# Sheet1.net
KiCad netlist of a schematic drawn in Altium Designer
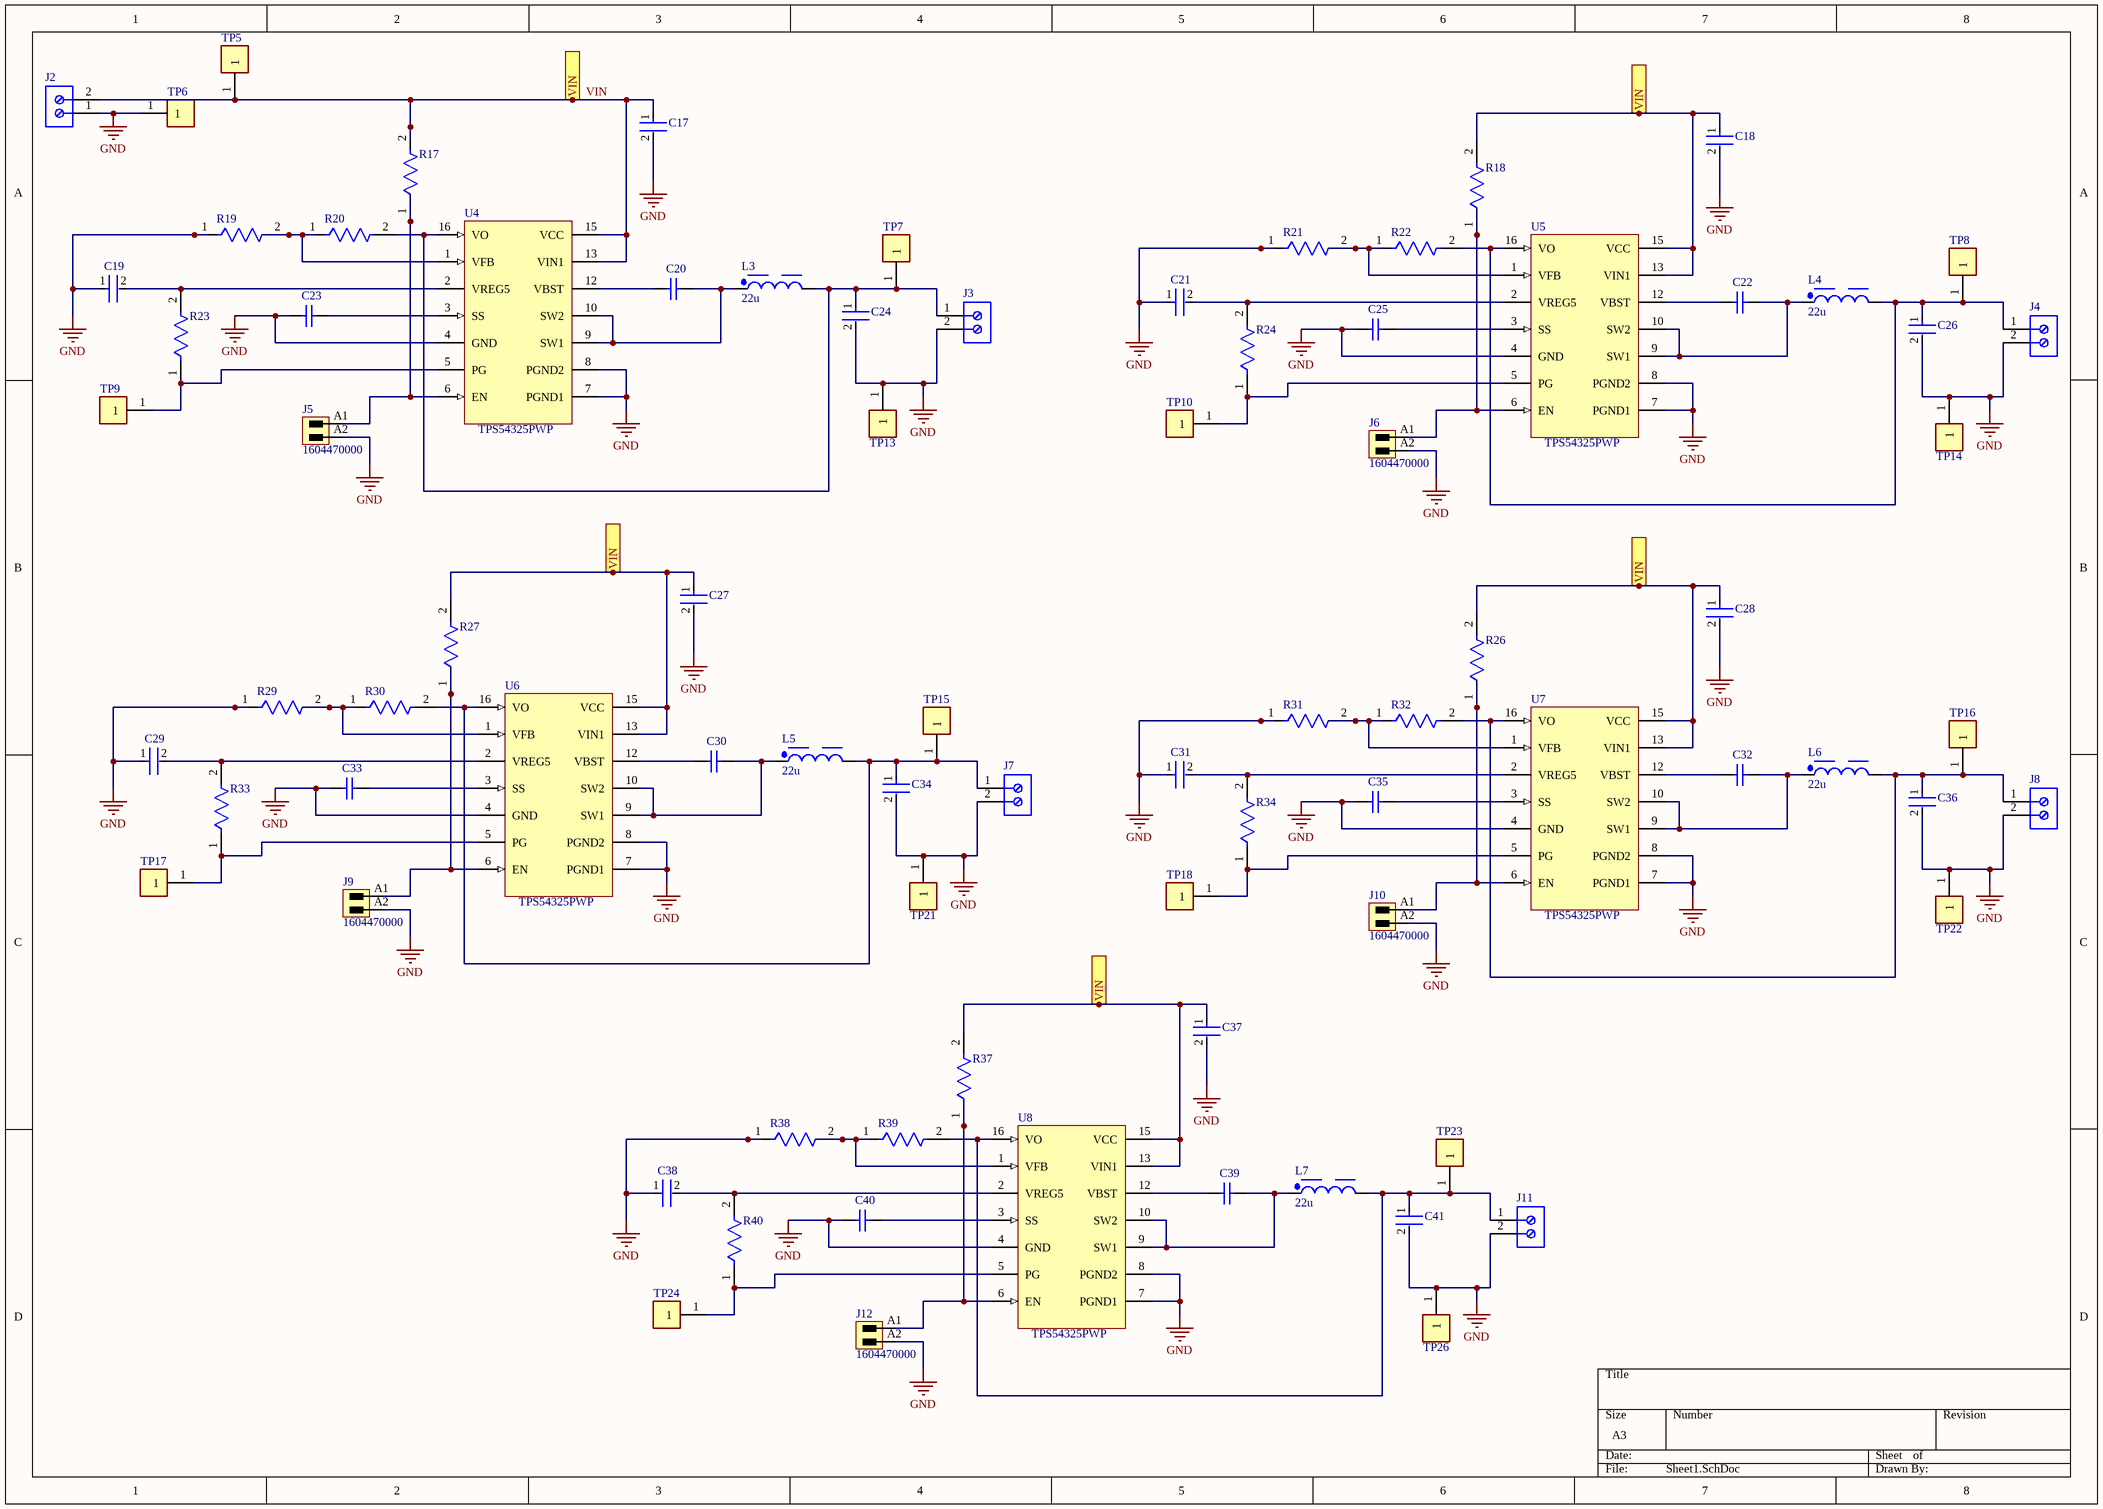
[diagram p0: Sheet1.SchDoc]

(export (version "E")
  (design (tool "Eeschema 10.0.6"))
  (components
    (comp (ref "C17")
      (value "C3216X5R1C106K160AA")
      (footprint "FP-C3216-160-0_2-IPC_C")
      (description "Multilayer Ceramic Capacitors 10uF ±10% 16V X5R SMD 1206")
      (fields (field (name "VOLTAGE") "16V") (field (name "TOLERANCE") "10%"))
      (libsource (lib "Altium Content Vault") (part "11868f565c42a9108669ba33697ecf6"))
    )
    (comp (ref "C18")
      (value "C3216X5R1C106K160AA")
      (footprint "FP-C3216-160-0_2-IPC_C")
      (description "Multilayer Ceramic Capacitors 10uF ±10% 16V X5R SMD 1206")
      (fields (field (name "VOLTAGE") "16V") (field (name "TOLERANCE") "10%"))
      (libsource (lib "Altium Content Vault") (part "11868f565c42a9108669ba33697ecf6"))
    )
    (comp (ref "C19")
      (value "0603YC105KAT2A")
      (footprint "FP-0603-L_1_6_0_15-W_0_81-IPC_C")
      (description "General Purpose Ceramic Capacitor, 0603, 1uF, 10%, X7R, 15%, 16V")
      (fields (field (name "TOLERANCE") "10%") (field (name "VOLTAGE") "16V"))
      (libsource (lib "Altium Content Vault") (part "02cd4be3c70576c341d710602a673aa"))
    )
    (comp (ref "C20")
      (value "GRM188R71H104KA93D")
      (footprint "CAPC1608X90X35ML10T15")
      (description "Chip Capacitor, 0.1 uF, +/- 10%, 50 V, -55 to 125 degC, 0603 (1608 Metric), RoHS, Tape and Reel")
      (fields (field (name "TOLERANCE") "10%") (field (name "VOLTAGE") "50V"))
      (libsource (lib "Altium Content Vault") (part "CAP-NP-2"))
    )
    (comp (ref "C21")
      (value "0603YC105KAT2A")
      (footprint "FP-0603-L_1_6_0_15-W_0_81-IPC_C")
      (description "General Purpose Ceramic Capacitor, 0603, 1uF, 10%, X7R, 15%, 16V")
      (fields (field (name "TOLERANCE") "10%") (field (name "VOLTAGE") "16V"))
      (libsource (lib "Altium Content Vault") (part "02cd4be3c70576c341d710602a673aa"))
    )
    (comp (ref "C22")
      (value "GRM188R71H104KA93D")
      (footprint "CAPC1608X90X35ML10T15")
      (description "Chip Capacitor, 0.1 uF, +/- 10%, 50 V, -55 to 125 degC, 0603 (1608 Metric), RoHS, Tape and Reel")
      (fields (field (name "TOLERANCE") "10%") (field (name "VOLTAGE") "50V"))
      (libsource (lib "Altium Content Vault") (part "CAP-NP-2"))
    )
    (comp (ref "C23")
      (value "GRM188R71H104KA93D")
      (footprint "CAPC1608X90X35ML10T15")
      (description "Chip Capacitor, 0.1 uF, +/- 10%, 50 V, -55 to 125 degC, 0603 (1608 Metric), RoHS, Tape and Reel")
      (fields (field (name "TOLERANCE") "10%") (field (name "VOLTAGE") "50V"))
      (libsource (lib "Altium Content Vault") (part "CAP-NP-2"))
    )
    (comp (ref "C24")
      (value "GRM21BR60J226ME39L")
      (footprint "FP-GRM21B-0_15-MFG")
      (description "Chip Multilayer Ceramic Capacitors for General Purpose, 0805, 22uF, X5R, 15%, 20%, 6.3V")
      (fields (field (name "VOLTAGE") "6.3V") (field (name "TOLERANCE") "20%"))
      (libsource (lib "Altium Content Vault") (part "b4654b650e69147ec39a6b967a45e02"))
    )
    (comp (ref "C25")
      (value "GRM188R71H104KA93D")
      (footprint "CAPC1608X90X35ML10T15")
      (description "Chip Capacitor, 0.1 uF, +/- 10%, 50 V, -55 to 125 degC, 0603 (1608 Metric), RoHS, Tape and Reel")
      (fields (field (name "TOLERANCE") "10%") (field (name "VOLTAGE") "50V"))
      (libsource (lib "Altium Content Vault") (part "CAP-NP-2"))
    )
    (comp (ref "C26")
      (value "GRM21BR60J226ME39L")
      (footprint "FP-GRM21B-0_15-MFG")
      (description "Chip Multilayer Ceramic Capacitors for General Purpose, 0805, 22uF, X5R, 15%, 20%, 6.3V")
      (fields (field (name "VOLTAGE") "6.3V") (field (name "TOLERANCE") "20%"))
      (libsource (lib "Altium Content Vault") (part "b4654b650e69147ec39a6b967a45e02"))
    )
    (comp (ref "C27")
      (value "C3216X5R1C106K160AA")
      (footprint "FP-C3216-160-0_2-IPC_C")
      (description "Multilayer Ceramic Capacitors 10uF ±10% 16V X5R SMD 1206")
      (fields (field (name "VOLTAGE") "16V") (field (name "TOLERANCE") "10%"))
      (libsource (lib "Altium Content Vault") (part "11868f565c42a9108669ba33697ecf6"))
    )
    (comp (ref "C28")
      (value "C3216X5R1C106K160AA")
      (footprint "FP-C3216-160-0_2-IPC_C")
      (description "Multilayer Ceramic Capacitors 10uF ±10% 16V X5R SMD 1206")
      (fields (field (name "VOLTAGE") "16V") (field (name "TOLERANCE") "10%"))
      (libsource (lib "Altium Content Vault") (part "11868f565c42a9108669ba33697ecf6"))
    )
    (comp (ref "C29")
      (value "0603YC105KAT2A")
      (footprint "FP-0603-L_1_6_0_15-W_0_81-IPC_C")
      (description "General Purpose Ceramic Capacitor, 0603, 1uF, 10%, X7R, 15%, 16V")
      (fields (field (name "TOLERANCE") "10%") (field (name "VOLTAGE") "16V"))
      (libsource (lib "Altium Content Vault") (part "02cd4be3c70576c341d710602a673aa"))
    )
    (comp (ref "C30")
      (value "GRM188R71H104KA93D")
      (footprint "CAPC1608X90X35ML10T15")
      (description "Chip Capacitor, 0.1 uF, +/- 10%, 50 V, -55 to 125 degC, 0603 (1608 Metric), RoHS, Tape and Reel")
      (fields (field (name "TOLERANCE") "10%") (field (name "VOLTAGE") "50V"))
      (libsource (lib "Altium Content Vault") (part "CAP-NP-2"))
    )
    (comp (ref "C31")
      (value "0603YC105KAT2A")
      (footprint "FP-0603-L_1_6_0_15-W_0_81-IPC_C")
      (description "General Purpose Ceramic Capacitor, 0603, 1uF, 10%, X7R, 15%, 16V")
      (fields (field (name "TOLERANCE") "10%") (field (name "VOLTAGE") "16V"))
      (libsource (lib "Altium Content Vault") (part "02cd4be3c70576c341d710602a673aa"))
    )
    (comp (ref "C32")
      (value "GRM188R71H104KA93D")
      (footprint "CAPC1608X90X35ML10T15")
      (description "Chip Capacitor, 0.1 uF, +/- 10%, 50 V, -55 to 125 degC, 0603 (1608 Metric), RoHS, Tape and Reel")
      (fields (field (name "TOLERANCE") "10%") (field (name "VOLTAGE") "50V"))
      (libsource (lib "Altium Content Vault") (part "CAP-NP-2"))
    )
    (comp (ref "C33")
      (value "GRM188R71H104KA93D")
      (footprint "CAPC1608X90X35ML10T15")
      (description "Chip Capacitor, 0.1 uF, +/- 10%, 50 V, -55 to 125 degC, 0603 (1608 Metric), RoHS, Tape and Reel")
      (fields (field (name "TOLERANCE") "10%") (field (name "VOLTAGE") "50V"))
      (libsource (lib "Altium Content Vault") (part "CAP-NP-2"))
    )
    (comp (ref "C34")
      (value "GRM21BR60J226ME39L")
      (footprint "FP-GRM21B-0_15-MFG")
      (description "Chip Multilayer Ceramic Capacitors for General Purpose, 0805, 22uF, X5R, 15%, 20%, 6.3V")
      (fields (field (name "VOLTAGE") "6.3V") (field (name "TOLERANCE") "20%"))
      (libsource (lib "Altium Content Vault") (part "b4654b650e69147ec39a6b967a45e02"))
    )
    (comp (ref "C35")
      (value "GRM188R71H104KA93D")
      (footprint "CAPC1608X90X35ML10T15")
      (description "Chip Capacitor, 0.1 uF, +/- 10%, 50 V, -55 to 125 degC, 0603 (1608 Metric), RoHS, Tape and Reel")
      (fields (field (name "TOLERANCE") "10%") (field (name "VOLTAGE") "50V"))
      (libsource (lib "Altium Content Vault") (part "CAP-NP-2"))
    )
    (comp (ref "C36")
      (value "GRM21BR60J226ME39L")
      (footprint "FP-GRM21B-0_15-MFG")
      (description "Chip Multilayer Ceramic Capacitors for General Purpose, 0805, 22uF, X5R, 15%, 20%, 6.3V")
      (fields (field (name "VOLTAGE") "6.3V") (field (name "TOLERANCE") "20%"))
      (libsource (lib "Altium Content Vault") (part "b4654b650e69147ec39a6b967a45e02"))
    )
    (comp (ref "C37")
      (value "C3216X5R1C106K160AA")
      (footprint "FP-C3216-160-0_2-IPC_C")
      (description "Multilayer Ceramic Capacitors 10uF ±10% 16V X5R SMD 1206")
      (fields (field (name "VOLTAGE") "16V") (field (name "TOLERANCE") "10%"))
      (libsource (lib "Altium Content Vault") (part "11868f565c42a9108669ba33697ecf6"))
    )
    (comp (ref "C38")
      (value "0603YC105KAT2A")
      (footprint "FP-0603-L_1_6_0_15-W_0_81-IPC_C")
      (description "General Purpose Ceramic Capacitor, 0603, 1uF, 10%, X7R, 15%, 16V")
      (fields (field (name "TOLERANCE") "10%") (field (name "VOLTAGE") "16V"))
      (libsource (lib "Altium Content Vault") (part "02cd4be3c70576c341d710602a673aa"))
    )
    (comp (ref "C39")
      (value "GRM188R71H104KA93D")
      (footprint "CAPC1608X90X35ML10T15")
      (description "Chip Capacitor, 0.1 uF, +/- 10%, 50 V, -55 to 125 degC, 0603 (1608 Metric), RoHS, Tape and Reel")
      (fields (field (name "TOLERANCE") "10%") (field (name "VOLTAGE") "50V"))
      (libsource (lib "Altium Content Vault") (part "CAP-NP-2"))
    )
    (comp (ref "C40")
      (value "GRM188R71H104KA93D")
      (footprint "CAPC1608X90X35ML10T15")
      (description "Chip Capacitor, 0.1 uF, +/- 10%, 50 V, -55 to 125 degC, 0603 (1608 Metric), RoHS, Tape and Reel")
      (fields (field (name "TOLERANCE") "10%") (field (name "VOLTAGE") "50V"))
      (libsource (lib "Altium Content Vault") (part "CAP-NP-2"))
    )
    (comp (ref "C41")
      (value "GRM21BR60J226ME39L")
      (footprint "FP-GRM21B-0_15-MFG")
      (description "Chip Multilayer Ceramic Capacitors for General Purpose, 0805, 22uF, X5R, 15%, 20%, 6.3V")
      (fields (field (name "VOLTAGE") "6.3V") (field (name "TOLERANCE") "20%"))
      (libsource (lib "Altium Content Vault") (part "b4654b650e69147ec39a6b967a45e02"))
    )
    (comp (ref "J2")
      (value "~")
      (footprint "TECO-282836-2_V")
      (description "Female Header, Pitch 5 mm, 1 x 2 Position, Height 10 mm, Tail Length 3.5 mm, Rohs, Bulk")
      (fields (field (name "VOLTAGE") "300V") (field (name "MANUFACTURER") "TE Connectivity"))
      (libsource (lib "Altium Content Vault") (part "CN-1P-F-TB2"))
    )
    (comp (ref "J3")
      (value "~")
      (footprint "TECO-282836-2_V")
      (description "Female Header, Pitch 5 mm, 1 x 2 Position, Height 10 mm, Tail Length 3.5 mm, Rohs, Bulk")
      (fields (field (name "VOLTAGE") "300V") (field (name "MANUFACTURER") "TE Connectivity"))
      (libsource (lib "Altium Content Vault") (part "CN-1P-F-TB2"))
    )
    (comp (ref "J4")
      (value "~")
      (footprint "TECO-282836-2_V")
      (description "Female Header, Pitch 5 mm, 1 x 2 Position, Height 10 mm, Tail Length 3.5 mm, Rohs, Bulk")
      (fields (field (name "VOLTAGE") "300V") (field (name "MANUFACTURER") "TE Connectivity"))
      (libsource (lib "Altium Content Vault") (part "CN-1P-F-TB2"))
    )
    (comp (ref "J5")
      (value "1604470000")
      (footprint "SL_3_50_180G_02")
      (description "OMNIMATE Signal - series BL/SL 3.50")
      (fields (field (name "MANUFACTURER") "Weidmueller"))
      (libsource (lib "Altium Content Vault") (part "Header_Male_02_1x02"))
    )
    (comp (ref "J6")
      (value "1604470000")
      (footprint "SL_3_50_180G_02")
      (description "OMNIMATE Signal - series BL/SL 3.50")
      (fields (field (name "MANUFACTURER") "Weidmueller"))
      (libsource (lib "Altium Content Vault") (part "Header_Male_02_1x02"))
    )
    (comp (ref "J7")
      (value "~")
      (footprint "TECO-282836-2_V")
      (description "Female Header, Pitch 5 mm, 1 x 2 Position, Height 10 mm, Tail Length 3.5 mm, Rohs, Bulk")
      (fields (field (name "VOLTAGE") "300V") (field (name "MANUFACTURER") "TE Connectivity"))
      (libsource (lib "Altium Content Vault") (part "CN-1P-F-TB2"))
    )
    (comp (ref "J8")
      (value "~")
      (footprint "TECO-282836-2_V")
      (description "Female Header, Pitch 5 mm, 1 x 2 Position, Height 10 mm, Tail Length 3.5 mm, Rohs, Bulk")
      (fields (field (name "VOLTAGE") "300V") (field (name "MANUFACTURER") "TE Connectivity"))
      (libsource (lib "Altium Content Vault") (part "CN-1P-F-TB2"))
    )
    (comp (ref "J9")
      (value "1604470000")
      (footprint "SL_3_50_180G_02")
      (description "OMNIMATE Signal - series BL/SL 3.50")
      (fields (field (name "MANUFACTURER") "Weidmueller"))
      (libsource (lib "Altium Content Vault") (part "Header_Male_02_1x02"))
    )
    (comp (ref "J10")
      (value "1604470000")
      (footprint "SL_3_50_180G_02")
      (description "OMNIMATE Signal - series BL/SL 3.50")
      (fields (field (name "MANUFACTURER") "Weidmueller"))
      (libsource (lib "Altium Content Vault") (part "Header_Male_02_1x02"))
    )
    (comp (ref "J11")
      (value "~")
      (footprint "TECO-282836-2_V")
      (description "Female Header, Pitch 5 mm, 1 x 2 Position, Height 10 mm, Tail Length 3.5 mm, Rohs, Bulk")
      (fields (field (name "VOLTAGE") "300V") (field (name "MANUFACTURER") "TE Connectivity"))
      (libsource (lib "Altium Content Vault") (part "CN-1P-F-TB2"))
    )
    (comp (ref "J12")
      (value "1604470000")
      (footprint "SL_3_50_180G_02")
      (description "OMNIMATE Signal - series BL/SL 3.50")
      (fields (field (name "MANUFACTURER") "Weidmueller"))
      (libsource (lib "Altium Content Vault") (part "Header_Male_02_1x02"))
    )
    (comp (ref "L3")
      (value "22u")
      (footprint "WE-PD_7332R")
      (fields (field (name "TOLERANCE") "20%"))
      (libsource (lib "Altium Content Vault") (part "Inductor - 2"))
    )
    (comp (ref "L4")
      (value "22u")
      (footprint "WE-PD_7332R")
      (fields (field (name "TOLERANCE") "20%"))
      (libsource (lib "Altium Content Vault") (part "Inductor - 2"))
    )
    (comp (ref "L5")
      (value "22u")
      (footprint "WE-PD_7332R")
      (fields (field (name "TOLERANCE") "20%"))
      (libsource (lib "Altium Content Vault") (part "Inductor - 2"))
    )
    (comp (ref "L6")
      (value "22u")
      (footprint "WE-PD_7332R")
      (fields (field (name "TOLERANCE") "20%"))
      (libsource (lib "Altium Content Vault") (part "Inductor - 2"))
    )
    (comp (ref "L7")
      (value "22u")
      (footprint "WE-PD_7332R")
      (fields (field (name "TOLERANCE") "20%"))
      (libsource (lib "Altium Content Vault") (part "Inductor - 2"))
    )
    (comp (ref "R17")
      (value "RR0816P-104-D")
      (footprint "FP-RR0816-IPC_A")
      (description "100kΩ ±0.5% 0.0625W 1/16W Chip Resistor 0603 (1608 Metric) Thin Film")
      (fields (field (name "TOLERANCE") "0.5%"))
      (libsource (lib "Altium Content Vault") (part "1029c3af85768c4190bb7ad29bc67b5"))
    )
    (comp (ref "R18")
      (value "RR0816P-104-D")
      (footprint "FP-RR0816-IPC_A")
      (description "100kΩ ±0.5% 0.0625W 1/16W Chip Resistor 0603 (1608 Metric) Thin Film")
      (fields (field (name "TOLERANCE") "0.5%"))
      (libsource (lib "Altium Content Vault") (part "1029c3af85768c4190bb7ad29bc67b5"))
    )
    (comp (ref "R19")
      (value "RR0816P-103-D")
      (footprint "FP-RR0816-MFG")
      (description "10kΩ ±0.5% 0.0625W 1/16W Chip Resistor 0603 (1608 Metric) Thin Film")
      (fields (field (name "TOLERANCE") "0.5%"))
      (libsource (lib "Altium Content Vault") (part "1029c3af85768c4190bb7ad29bc67b5"))
    )
    (comp (ref "R20")
      (value "RR0816P-203-D")
      (footprint "FP-RR0816-MFG")
      (description "20kΩ ±0.5% 0.0625W 1/16W Chip Resistor 0603 (1608 Metric) Thin Film")
      (fields (field (name "TOLERANCE") "0.5%"))
      (libsource (lib "Altium Content Vault") (part "1029c3af85768c4190bb7ad29bc67b5"))
    )
    (comp (ref "R21")
      (value "RR0816P-103-D")
      (footprint "FP-RR0816-MFG")
      (description "10kΩ ±0.5% 0.0625W 1/16W Chip Resistor 0603 (1608 Metric) Thin Film")
      (fields (field (name "TOLERANCE") "0.5%"))
      (libsource (lib "Altium Content Vault") (part "1029c3af85768c4190bb7ad29bc67b5"))
    )
    (comp (ref "R22")
      (value "RR0816P-203-D")
      (footprint "FP-RR0816-MFG")
      (description "20kΩ ±0.5% 0.0625W 1/16W Chip Resistor 0603 (1608 Metric) Thin Film")
      (fields (field (name "TOLERANCE") "0.5%"))
      (libsource (lib "Altium Content Vault") (part "1029c3af85768c4190bb7ad29bc67b5"))
    )
    (comp (ref "R23")
      (value "RR0816P-104-D")
      (footprint "FP-RR0816-IPC_A")
      (description "100kΩ ±0.5% 0.0625W 1/16W Chip Resistor 0603 (1608 Metric) Thin Film")
      (fields (field (name "TOLERANCE") "0.5%"))
      (libsource (lib "Altium Content Vault") (part "1029c3af85768c4190bb7ad29bc67b5"))
    )
    (comp (ref "R24")
      (value "RR0816P-104-D")
      (footprint "FP-RR0816-IPC_A")
      (description "100kΩ ±0.5% 0.0625W 1/16W Chip Resistor 0603 (1608 Metric) Thin Film")
      (fields (field (name "TOLERANCE") "0.5%"))
      (libsource (lib "Altium Content Vault") (part "1029c3af85768c4190bb7ad29bc67b5"))
    )
    (comp (ref "R26")
      (value "RR0816P-104-D")
      (footprint "FP-RR0816-IPC_A")
      (description "100kΩ ±0.5% 0.0625W 1/16W Chip Resistor 0603 (1608 Metric) Thin Film")
      (fields (field (name "TOLERANCE") "0.5%"))
      (libsource (lib "Altium Content Vault") (part "1029c3af85768c4190bb7ad29bc67b5"))
    )
    (comp (ref "R27")
      (value "RR0816P-104-D")
      (footprint "FP-RR0816-IPC_A")
      (description "100kΩ ±0.5% 0.0625W 1/16W Chip Resistor 0603 (1608 Metric) Thin Film")
      (fields (field (name "TOLERANCE") "0.5%"))
      (libsource (lib "Altium Content Vault") (part "1029c3af85768c4190bb7ad29bc67b5"))
    )
    (comp (ref "R29")
      (value "RR0816P-103-D")
      (footprint "FP-RR0816-MFG")
      (description "10kΩ ±0.5% 0.0625W 1/16W Chip Resistor 0603 (1608 Metric) Thin Film")
      (fields (field (name "TOLERANCE") "0.5%"))
      (libsource (lib "Altium Content Vault") (part "1029c3af85768c4190bb7ad29bc67b5"))
    )
    (comp (ref "R30")
      (value "RR0816P-203-D")
      (footprint "FP-RR0816-MFG")
      (description "20kΩ ±0.5% 0.0625W 1/16W Chip Resistor 0603 (1608 Metric) Thin Film")
      (fields (field (name "TOLERANCE") "0.5%"))
      (libsource (lib "Altium Content Vault") (part "1029c3af85768c4190bb7ad29bc67b5"))
    )
    (comp (ref "R31")
      (value "RR0816P-103-D")
      (footprint "FP-RR0816-MFG")
      (description "10kΩ ±0.5% 0.0625W 1/16W Chip Resistor 0603 (1608 Metric) Thin Film")
      (fields (field (name "TOLERANCE") "0.5%"))
      (libsource (lib "Altium Content Vault") (part "1029c3af85768c4190bb7ad29bc67b5"))
    )
    (comp (ref "R32")
      (value "RR0816P-203-D")
      (footprint "FP-RR0816-MFG")
      (description "20kΩ ±0.5% 0.0625W 1/16W Chip Resistor 0603 (1608 Metric) Thin Film")
      (fields (field (name "TOLERANCE") "0.5%"))
      (libsource (lib "Altium Content Vault") (part "1029c3af85768c4190bb7ad29bc67b5"))
    )
    (comp (ref "R33")
      (value "RR0816P-104-D")
      (footprint "FP-RR0816-IPC_A")
      (description "100kΩ ±0.5% 0.0625W 1/16W Chip Resistor 0603 (1608 Metric) Thin Film")
      (fields (field (name "TOLERANCE") "0.5%"))
      (libsource (lib "Altium Content Vault") (part "1029c3af85768c4190bb7ad29bc67b5"))
    )
    (comp (ref "R34")
      (value "RR0816P-104-D")
      (footprint "FP-RR0816-IPC_A")
      (description "100kΩ ±0.5% 0.0625W 1/16W Chip Resistor 0603 (1608 Metric) Thin Film")
      (fields (field (name "TOLERANCE") "0.5%"))
      (libsource (lib "Altium Content Vault") (part "1029c3af85768c4190bb7ad29bc67b5"))
    )
    (comp (ref "R37")
      (value "RR0816P-104-D")
      (footprint "FP-RR0816-IPC_A")
      (description "100kΩ ±0.5% 0.0625W 1/16W Chip Resistor 0603 (1608 Metric) Thin Film")
      (fields (field (name "TOLERANCE") "0.5%"))
      (libsource (lib "Altium Content Vault") (part "1029c3af85768c4190bb7ad29bc67b5"))
    )
    (comp (ref "R38")
      (value "RR0816P-103-D")
      (footprint "FP-RR0816-MFG")
      (description "10kΩ ±0.5% 0.0625W 1/16W Chip Resistor 0603 (1608 Metric) Thin Film")
      (fields (field (name "TOLERANCE") "0.5%"))
      (libsource (lib "Altium Content Vault") (part "1029c3af85768c4190bb7ad29bc67b5"))
    )
    (comp (ref "R39")
      (value "RR0816P-203-D")
      (footprint "FP-RR0816-MFG")
      (description "20kΩ ±0.5% 0.0625W 1/16W Chip Resistor 0603 (1608 Metric) Thin Film")
      (fields (field (name "TOLERANCE") "0.5%"))
      (libsource (lib "Altium Content Vault") (part "1029c3af85768c4190bb7ad29bc67b5"))
    )
    (comp (ref "R40")
      (value "RR0816P-104-D")
      (footprint "FP-RR0816-IPC_A")
      (description "100kΩ ±0.5% 0.0625W 1/16W Chip Resistor 0603 (1608 Metric) Thin Film")
      (fields (field (name "TOLERANCE") "0.5%"))
      (libsource (lib "Altium Content Vault") (part "1029c3af85768c4190bb7ad29bc67b5"))
    )
    (comp (ref "TP5")
      (value "~")
      (footprint "FP-5000-MFG")
      (description "PC TEST POINT MINIATURE RED")
      (libsource (lib "") (part "1e4615820a309e3ce90f9e6d957b7fa_2"))
    )
    (comp (ref "TP6")
      (value "~")
      (footprint "FP-5001-MFG")
      (description "PC TEST POINT MINIATURE BLACK")
      (libsource (lib "") (part "1e4615820a309e3ce90f9e6d957b7fa_3"))
    )
    (comp (ref "TP7")
      (value "~")
      (footprint "FP-5000-MFG")
      (description "PC TEST POINT MINIATURE RED")
      (libsource (lib "") (part "1e4615820a309e3ce90f9e6d957b7fa_2"))
    )
    (comp (ref "TP8")
      (value "~")
      (footprint "FP-5000-MFG")
      (description "PC TEST POINT MINIATURE RED")
      (libsource (lib "") (part "1e4615820a309e3ce90f9e6d957b7fa_2"))
    )
    (comp (ref "TP9")
      (value "~")
      (footprint "FP-5000-MFG")
      (description "PC TEST POINT MINIATURE RED")
      (libsource (lib "Altium Content Vault") (part "1e4615820a309e3ce90f9e6d957b7fa"))
    )
    (comp (ref "TP10")
      (value "~")
      (footprint "FP-5000-MFG")
      (description "PC TEST POINT MINIATURE RED")
      (libsource (lib "Altium Content Vault") (part "1e4615820a309e3ce90f9e6d957b7fa"))
    )
    (comp (ref "TP13")
      (value "~")
      (footprint "FP-5001-MFG")
      (description "PC TEST POINT MINIATURE BLACK")
      (libsource (lib "") (part "1e4615820a309e3ce90f9e6d957b7fa_1"))
    )
    (comp (ref "TP14")
      (value "~")
      (footprint "FP-5001-MFG")
      (description "PC TEST POINT MINIATURE BLACK")
      (libsource (lib "") (part "1e4615820a309e3ce90f9e6d957b7fa_1"))
    )
    (comp (ref "TP15")
      (value "~")
      (footprint "FP-5000-MFG")
      (description "PC TEST POINT MINIATURE RED")
      (libsource (lib "") (part "1e4615820a309e3ce90f9e6d957b7fa_2"))
    )
    (comp (ref "TP16")
      (value "~")
      (footprint "FP-5000-MFG")
      (description "PC TEST POINT MINIATURE RED")
      (libsource (lib "") (part "1e4615820a309e3ce90f9e6d957b7fa_2"))
    )
    (comp (ref "TP17")
      (value "~")
      (footprint "FP-5000-MFG")
      (description "PC TEST POINT MINIATURE RED")
      (libsource (lib "Altium Content Vault") (part "1e4615820a309e3ce90f9e6d957b7fa"))
    )
    (comp (ref "TP18")
      (value "~")
      (footprint "FP-5000-MFG")
      (description "PC TEST POINT MINIATURE RED")
      (libsource (lib "Altium Content Vault") (part "1e4615820a309e3ce90f9e6d957b7fa"))
    )
    (comp (ref "TP21")
      (value "~")
      (footprint "FP-5001-MFG")
      (description "PC TEST POINT MINIATURE BLACK")
      (libsource (lib "") (part "1e4615820a309e3ce90f9e6d957b7fa_1"))
    )
    (comp (ref "TP22")
      (value "~")
      (footprint "FP-5001-MFG")
      (description "PC TEST POINT MINIATURE BLACK")
      (libsource (lib "") (part "1e4615820a309e3ce90f9e6d957b7fa_1"))
    )
    (comp (ref "TP23")
      (value "~")
      (footprint "FP-5000-MFG")
      (description "PC TEST POINT MINIATURE RED")
      (libsource (lib "") (part "1e4615820a309e3ce90f9e6d957b7fa_2"))
    )
    (comp (ref "TP24")
      (value "~")
      (footprint "FP-5000-MFG")
      (description "PC TEST POINT MINIATURE RED")
      (libsource (lib "Altium Content Vault") (part "1e4615820a309e3ce90f9e6d957b7fa"))
    )
    (comp (ref "TP26")
      (value "~")
      (footprint "FP-5001-MFG")
      (description "PC TEST POINT MINIATURE BLACK")
      (libsource (lib "") (part "1e4615820a309e3ce90f9e6d957b7fa_1"))
    )
    (comp (ref "U4")
      (value "TPS54325PWP")
      (footprint "RGT0016C_V")
      (fields (field (name "PARTNUMBER") "TPS54326RGTR") (field (name "MANUFACTURER") "Texas Instruments"))
      (libsource (lib "Altium Content Vault") (part "TI-TPS54326RGT16-1700X1700TP"))
    )
    (comp (ref "U5")
      (value "TPS54325PWP")
      (footprint "RGT0016C_V")
      (fields (field (name "PARTNUMBER") "TPS54326RGTR") (field (name "MANUFACTURER") "Texas Instruments"))
      (libsource (lib "Altium Content Vault") (part "TI-TPS54326RGT16-1700X1700TP"))
    )
    (comp (ref "U6")
      (value "TPS54325PWP")
      (footprint "RGT0016C_V")
      (fields (field (name "PARTNUMBER") "TPS54326RGTR") (field (name "MANUFACTURER") "Texas Instruments"))
      (libsource (lib "Altium Content Vault") (part "TI-TPS54326RGT16-1700X1700TP"))
    )
    (comp (ref "U7")
      (value "TPS54325PWP")
      (footprint "RGT0016C_V")
      (fields (field (name "PARTNUMBER") "TPS54326RGTR") (field (name "MANUFACTURER") "Texas Instruments"))
      (libsource (lib "Altium Content Vault") (part "TI-TPS54326RGT16-1700X1700TP"))
    )
    (comp (ref "U8")
      (value "TPS54325PWP")
      (footprint "RGT0016C_V")
      (fields (field (name "PARTNUMBER") "TPS54326RGTR") (field (name "MANUFACTURER") "Texas Instruments"))
      (libsource (lib "Altium Content Vault") (part "TI-TPS54326RGT16-1700X1700TP"))
    )
  )
  (nets
    (net (code "1") (name "/VIN") (class "Default")
      (node (ref "C17") (pin "1") (pinfunction "1_1") (pintype "passive"))
      (node (ref "C18") (pin "1") (pinfunction "1_1") (pintype "passive"))
      (node (ref "C27") (pin "1") (pinfunction "1_1") (pintype "passive"))
      (node (ref "C28") (pin "1") (pinfunction "1_1") (pintype "passive"))
      (node (ref "C37") (pin "1") (pinfunction "1_1") (pintype "passive"))
      (node (ref "J2") (pin "2") (pinfunction "2_2") (pintype "passive"))
      (node (ref "R17") (pin "2") (pinfunction "2_2") (pintype "passive"))
      (node (ref "R18") (pin "2") (pinfunction "2_2") (pintype "passive"))
      (node (ref "R26") (pin "2") (pinfunction "2_2") (pintype "passive"))
      (node (ref "R27") (pin "2") (pinfunction "2_2") (pintype "passive"))
      (node (ref "R37") (pin "2") (pinfunction "2_2") (pintype "passive"))
      (node (ref "TP5") (pin "1") (pinfunction "1_1") (pintype "passive"))
      (node (ref "U4") (pin "13") (pinfunction "VIN1_13") (pintype "power_in"))
      (node (ref "U4") (pin "15") (pinfunction "VCC_15") (pintype "power_in"))
      (node (ref "U5") (pin "13") (pinfunction "VIN1_13") (pintype "power_in"))
      (node (ref "U5") (pin "15") (pinfunction "VCC_15") (pintype "power_in"))
      (node (ref "U6") (pin "13") (pinfunction "VIN1_13") (pintype "power_in"))
      (node (ref "U6") (pin "15") (pinfunction "VCC_15") (pintype "power_in"))
      (node (ref "U7") (pin "13") (pinfunction "VIN1_13") (pintype "power_in"))
      (node (ref "U7") (pin "15") (pinfunction "VCC_15") (pintype "power_in"))
      (node (ref "U8") (pin "13") (pinfunction "VIN1_13") (pintype "power_in"))
      (node (ref "U8") (pin "15") (pinfunction "VCC_15") (pintype "power_in"))
    )
    (net (code "2") (name "GND") (class "Default")
      (node (ref "C17") (pin "2") (pinfunction "2_2") (pintype "passive"))
      (node (ref "C18") (pin "2") (pinfunction "2_2") (pintype "passive"))
      (node (ref "C19") (pin "1") (pinfunction "1_1") (pintype "passive"))
      (node (ref "C21") (pin "1") (pinfunction "1_1") (pintype "passive"))
      (node (ref "C23") (pin "1") (pinfunction "1_1") (pintype "passive"))
      (node (ref "C24") (pin "2") (pinfunction "2_2") (pintype "passive"))
      (node (ref "C25") (pin "1") (pinfunction "1_1") (pintype "passive"))
      (node (ref "C26") (pin "2") (pinfunction "2_2") (pintype "passive"))
      (node (ref "C27") (pin "2") (pinfunction "2_2") (pintype "passive"))
      (node (ref "C28") (pin "2") (pinfunction "2_2") (pintype "passive"))
      (node (ref "C29") (pin "1") (pinfunction "1_1") (pintype "passive"))
      (node (ref "C31") (pin "1") (pinfunction "1_1") (pintype "passive"))
      (node (ref "C33") (pin "1") (pinfunction "1_1") (pintype "passive"))
      (node (ref "C34") (pin "2") (pinfunction "2_2") (pintype "passive"))
      (node (ref "C35") (pin "1") (pinfunction "1_1") (pintype "passive"))
      (node (ref "C36") (pin "2") (pinfunction "2_2") (pintype "passive"))
      (node (ref "C37") (pin "2") (pinfunction "2_2") (pintype "passive"))
      (node (ref "C38") (pin "1") (pinfunction "1_1") (pintype "passive"))
      (node (ref "C40") (pin "1") (pinfunction "1_1") (pintype "passive"))
      (node (ref "C41") (pin "2") (pinfunction "2_2") (pintype "passive"))
      (node (ref "J10") (pin "A2") (pinfunction "A2_A2") (pintype "passive"))
      (node (ref "J11") (pin "2") (pinfunction "2_2") (pintype "passive"))
      (node (ref "J12") (pin "A2") (pinfunction "A2_A2") (pintype "passive"))
      (node (ref "J2") (pin "1") (pinfunction "1_1") (pintype "passive"))
      (node (ref "J3") (pin "2") (pinfunction "2_2") (pintype "passive"))
      (node (ref "J4") (pin "2") (pinfunction "2_2") (pintype "passive"))
      (node (ref "J5") (pin "A2") (pinfunction "A2_A2") (pintype "passive"))
      (node (ref "J6") (pin "A2") (pinfunction "A2_A2") (pintype "passive"))
      (node (ref "J7") (pin "2") (pinfunction "2_2") (pintype "passive"))
      (node (ref "J8") (pin "2") (pinfunction "2_2") (pintype "passive"))
      (node (ref "J9") (pin "A2") (pinfunction "A2_A2") (pintype "passive"))
      (node (ref "R19") (pin "1") (pinfunction "1_1") (pintype "passive"))
      (node (ref "R21") (pin "1") (pinfunction "1_1") (pintype "passive"))
      (node (ref "R29") (pin "1") (pinfunction "1_1") (pintype "passive"))
      (node (ref "R31") (pin "1") (pinfunction "1_1") (pintype "passive"))
      (node (ref "R38") (pin "1") (pinfunction "1_1") (pintype "passive"))
      (node (ref "TP13") (pin "1") (pinfunction "1_1") (pintype "passive"))
      (node (ref "TP14") (pin "1") (pinfunction "1_1") (pintype "passive"))
      (node (ref "TP21") (pin "1") (pinfunction "1_1") (pintype "passive"))
      (node (ref "TP22") (pin "1") (pinfunction "1_1") (pintype "passive"))
      (node (ref "TP26") (pin "1") (pinfunction "1_1") (pintype "passive"))
      (node (ref "TP6") (pin "1") (pinfunction "1_1") (pintype "passive"))
      (node (ref "U4") (pin "4") (pinfunction "GND_4") (pintype "power_in"))
      (node (ref "U4") (pin "7") (pinfunction "PGND1_7") (pintype "power_in"))
      (node (ref "U4") (pin "8") (pinfunction "PGND2_8") (pintype "power_in"))
      (node (ref "U5") (pin "4") (pinfunction "GND_4") (pintype "power_in"))
      (node (ref "U5") (pin "7") (pinfunction "PGND1_7") (pintype "power_in"))
      (node (ref "U5") (pin "8") (pinfunction "PGND2_8") (pintype "power_in"))
      (node (ref "U6") (pin "4") (pinfunction "GND_4") (pintype "power_in"))
      (node (ref "U6") (pin "7") (pinfunction "PGND1_7") (pintype "power_in"))
      (node (ref "U6") (pin "8") (pinfunction "PGND2_8") (pintype "power_in"))
      (node (ref "U7") (pin "4") (pinfunction "GND_4") (pintype "power_in"))
      (node (ref "U7") (pin "7") (pinfunction "PGND1_7") (pintype "power_in"))
      (node (ref "U7") (pin "8") (pinfunction "PGND2_8") (pintype "power_in"))
      (node (ref "U8") (pin "4") (pinfunction "GND_4") (pintype "power_in"))
      (node (ref "U8") (pin "7") (pinfunction "PGND1_7") (pintype "power_in"))
      (node (ref "U8") (pin "8") (pinfunction "PGND2_8") (pintype "power_in"))
    )
    (net (code "3") (name "Net-(U4-EN)") (class "Default")
      (node (ref "J5") (pin "A1") (pinfunction "A1_A1") (pintype "passive"))
      (node (ref "R17") (pin "1") (pinfunction "1_1") (pintype "passive"))
      (node (ref "U4") (pin "6") (pinfunction "EN_6") (pintype "input"))
    )
    (net (code "4") (name "Net-(U4-PG)") (class "Default")
      (node (ref "R23") (pin "1") (pinfunction "1_1") (pintype "passive"))
      (node (ref "TP9") (pin "1") (pinfunction "1_1") (pintype "passive"))
      (node (ref "U4") (pin "5") (pinfunction "PG_5") (pintype "open_collector"))
    )
    (net (code "5") (name "Net-(U4-SS)") (class "Default")
      (node (ref "C23") (pin "2") (pinfunction "2_2") (pintype "passive"))
      (node (ref "U4") (pin "3") (pinfunction "SS_3") (pintype "input"))
    )
    (net (code "6") (name "Net-(U4-SW1)") (class "Default")
      (node (ref "C20") (pin "2") (pinfunction "2_2") (pintype "passive"))
      (node (ref "L3") (pin "1") (pinfunction "1_1") (pintype "passive"))
      (node (ref "U4") (pin "10") (pinfunction "SW2_10") (pintype "power_in"))
      (node (ref "U4") (pin "9") (pinfunction "SW1_9") (pintype "power_in"))
    )
    (net (code "7") (name "Net-(U4-VBST)") (class "Default")
      (node (ref "C20") (pin "1") (pinfunction "1_1") (pintype "passive"))
      (node (ref "U4") (pin "12") (pinfunction "VBST_12") (pintype "passive"))
    )
    (net (code "8") (name "Net-(U4-VFB)") (class "Default")
      (node (ref "R19") (pin "2") (pinfunction "2_2") (pintype "passive"))
      (node (ref "R20") (pin "1") (pinfunction "1_1") (pintype "passive"))
      (node (ref "U4") (pin "1") (pinfunction "VFB_1") (pintype "input"))
    )
    (net (code "9") (name "Net-(U4-VO)") (class "Default")
      (node (ref "C24") (pin "1") (pinfunction "1_1") (pintype "passive"))
      (node (ref "J3") (pin "1") (pinfunction "1_1") (pintype "passive"))
      (node (ref "L3") (pin "2") (pinfunction "2_2") (pintype "passive"))
      (node (ref "R20") (pin "2") (pinfunction "2_2") (pintype "passive"))
      (node (ref "TP7") (pin "1") (pinfunction "1_1") (pintype "passive"))
      (node (ref "U4") (pin "16") (pinfunction "VO_16") (pintype "input"))
    )
    (net (code "10") (name "Net-(U4-VREG5)") (class "Default")
      (node (ref "C19") (pin "2") (pinfunction "2_2") (pintype "passive"))
      (node (ref "R23") (pin "2") (pinfunction "2_2") (pintype "passive"))
      (node (ref "U4") (pin "2") (pinfunction "VREG5_2") (pintype "power_in"))
    )
    (net (code "11") (name "Net-(U5-EN)") (class "Default")
      (node (ref "J6") (pin "A1") (pinfunction "A1_A1") (pintype "passive"))
      (node (ref "R18") (pin "1") (pinfunction "1_1") (pintype "passive"))
      (node (ref "U5") (pin "6") (pinfunction "EN_6") (pintype "input"))
    )
    (net (code "12") (name "Net-(U5-PG)") (class "Default")
      (node (ref "R24") (pin "1") (pinfunction "1_1") (pintype "passive"))
      (node (ref "TP10") (pin "1") (pinfunction "1_1") (pintype "passive"))
      (node (ref "U5") (pin "5") (pinfunction "PG_5") (pintype "open_collector"))
    )
    (net (code "13") (name "Net-(U5-SS)") (class "Default")
      (node (ref "C25") (pin "2") (pinfunction "2_2") (pintype "passive"))
      (node (ref "U5") (pin "3") (pinfunction "SS_3") (pintype "input"))
    )
    (net (code "14") (name "Net-(U5-SW1)") (class "Default")
      (node (ref "C22") (pin "2") (pinfunction "2_2") (pintype "passive"))
      (node (ref "L4") (pin "1") (pinfunction "1_1") (pintype "passive"))
      (node (ref "U5") (pin "10") (pinfunction "SW2_10") (pintype "power_in"))
      (node (ref "U5") (pin "9") (pinfunction "SW1_9") (pintype "power_in"))
    )
    (net (code "15") (name "Net-(U5-VBST)") (class "Default")
      (node (ref "C22") (pin "1") (pinfunction "1_1") (pintype "passive"))
      (node (ref "U5") (pin "12") (pinfunction "VBST_12") (pintype "passive"))
    )
    (net (code "16") (name "Net-(U5-VFB)") (class "Default")
      (node (ref "R21") (pin "2") (pinfunction "2_2") (pintype "passive"))
      (node (ref "R22") (pin "1") (pinfunction "1_1") (pintype "passive"))
      (node (ref "U5") (pin "1") (pinfunction "VFB_1") (pintype "input"))
    )
    (net (code "17") (name "Net-(U5-VO)") (class "Default")
      (node (ref "C26") (pin "1") (pinfunction "1_1") (pintype "passive"))
      (node (ref "J4") (pin "1") (pinfunction "1_1") (pintype "passive"))
      (node (ref "L4") (pin "2") (pinfunction "2_2") (pintype "passive"))
      (node (ref "R22") (pin "2") (pinfunction "2_2") (pintype "passive"))
      (node (ref "TP8") (pin "1") (pinfunction "1_1") (pintype "passive"))
      (node (ref "U5") (pin "16") (pinfunction "VO_16") (pintype "input"))
    )
    (net (code "18") (name "Net-(U5-VREG5)") (class "Default")
      (node (ref "C21") (pin "2") (pinfunction "2_2") (pintype "passive"))
      (node (ref "R24") (pin "2") (pinfunction "2_2") (pintype "passive"))
      (node (ref "U5") (pin "2") (pinfunction "VREG5_2") (pintype "power_in"))
    )
    (net (code "19") (name "Net-(U6-EN)") (class "Default")
      (node (ref "J9") (pin "A1") (pinfunction "A1_A1") (pintype "passive"))
      (node (ref "R27") (pin "1") (pinfunction "1_1") (pintype "passive"))
      (node (ref "U6") (pin "6") (pinfunction "EN_6") (pintype "input"))
    )
    (net (code "20") (name "Net-(U6-PG)") (class "Default")
      (node (ref "R33") (pin "1") (pinfunction "1_1") (pintype "passive"))
      (node (ref "TP17") (pin "1") (pinfunction "1_1") (pintype "passive"))
      (node (ref "U6") (pin "5") (pinfunction "PG_5") (pintype "open_collector"))
    )
    (net (code "21") (name "Net-(U6-SS)") (class "Default")
      (node (ref "C33") (pin "2") (pinfunction "2_2") (pintype "passive"))
      (node (ref "U6") (pin "3") (pinfunction "SS_3") (pintype "input"))
    )
    (net (code "22") (name "Net-(U6-SW1)") (class "Default")
      (node (ref "C30") (pin "2") (pinfunction "2_2") (pintype "passive"))
      (node (ref "L5") (pin "1") (pinfunction "1_1") (pintype "passive"))
      (node (ref "U6") (pin "10") (pinfunction "SW2_10") (pintype "power_in"))
      (node (ref "U6") (pin "9") (pinfunction "SW1_9") (pintype "power_in"))
    )
    (net (code "23") (name "Net-(U6-VBST)") (class "Default")
      (node (ref "C30") (pin "1") (pinfunction "1_1") (pintype "passive"))
      (node (ref "U6") (pin "12") (pinfunction "VBST_12") (pintype "passive"))
    )
    (net (code "24") (name "Net-(U6-VFB)") (class "Default")
      (node (ref "R29") (pin "2") (pinfunction "2_2") (pintype "passive"))
      (node (ref "R30") (pin "1") (pinfunction "1_1") (pintype "passive"))
      (node (ref "U6") (pin "1") (pinfunction "VFB_1") (pintype "input"))
    )
    (net (code "25") (name "Net-(U6-VO)") (class "Default")
      (node (ref "C34") (pin "1") (pinfunction "1_1") (pintype "passive"))
      (node (ref "J7") (pin "1") (pinfunction "1_1") (pintype "passive"))
      (node (ref "L5") (pin "2") (pinfunction "2_2") (pintype "passive"))
      (node (ref "R30") (pin "2") (pinfunction "2_2") (pintype "passive"))
      (node (ref "TP15") (pin "1") (pinfunction "1_1") (pintype "passive"))
      (node (ref "U6") (pin "16") (pinfunction "VO_16") (pintype "input"))
    )
    (net (code "26") (name "Net-(U6-VREG5)") (class "Default")
      (node (ref "C29") (pin "2") (pinfunction "2_2") (pintype "passive"))
      (node (ref "R33") (pin "2") (pinfunction "2_2") (pintype "passive"))
      (node (ref "U6") (pin "2") (pinfunction "VREG5_2") (pintype "power_in"))
    )
    (net (code "27") (name "Net-(U7-EN)") (class "Default")
      (node (ref "J10") (pin "A1") (pinfunction "A1_A1") (pintype "passive"))
      (node (ref "R26") (pin "1") (pinfunction "1_1") (pintype "passive"))
      (node (ref "U7") (pin "6") (pinfunction "EN_6") (pintype "input"))
    )
    (net (code "28") (name "Net-(U7-PG)") (class "Default")
      (node (ref "R34") (pin "1") (pinfunction "1_1") (pintype "passive"))
      (node (ref "TP18") (pin "1") (pinfunction "1_1") (pintype "passive"))
      (node (ref "U7") (pin "5") (pinfunction "PG_5") (pintype "open_collector"))
    )
    (net (code "29") (name "Net-(U7-SS)") (class "Default")
      (node (ref "C35") (pin "2") (pinfunction "2_2") (pintype "passive"))
      (node (ref "U7") (pin "3") (pinfunction "SS_3") (pintype "input"))
    )
    (net (code "30") (name "Net-(U7-SW1)") (class "Default")
      (node (ref "C32") (pin "2") (pinfunction "2_2") (pintype "passive"))
      (node (ref "L6") (pin "1") (pinfunction "1_1") (pintype "passive"))
      (node (ref "U7") (pin "10") (pinfunction "SW2_10") (pintype "power_in"))
      (node (ref "U7") (pin "9") (pinfunction "SW1_9") (pintype "power_in"))
    )
    (net (code "31") (name "Net-(U7-VBST)") (class "Default")
      (node (ref "C32") (pin "1") (pinfunction "1_1") (pintype "passive"))
      (node (ref "U7") (pin "12") (pinfunction "VBST_12") (pintype "passive"))
    )
    (net (code "32") (name "Net-(U7-VFB)") (class "Default")
      (node (ref "R31") (pin "2") (pinfunction "2_2") (pintype "passive"))
      (node (ref "R32") (pin "1") (pinfunction "1_1") (pintype "passive"))
      (node (ref "U7") (pin "1") (pinfunction "VFB_1") (pintype "input"))
    )
    (net (code "33") (name "Net-(U7-VO)") (class "Default")
      (node (ref "C36") (pin "1") (pinfunction "1_1") (pintype "passive"))
      (node (ref "J8") (pin "1") (pinfunction "1_1") (pintype "passive"))
      (node (ref "L6") (pin "2") (pinfunction "2_2") (pintype "passive"))
      (node (ref "R32") (pin "2") (pinfunction "2_2") (pintype "passive"))
      (node (ref "TP16") (pin "1") (pinfunction "1_1") (pintype "passive"))
      (node (ref "U7") (pin "16") (pinfunction "VO_16") (pintype "input"))
    )
    (net (code "34") (name "Net-(U7-VREG5)") (class "Default")
      (node (ref "C31") (pin "2") (pinfunction "2_2") (pintype "passive"))
      (node (ref "R34") (pin "2") (pinfunction "2_2") (pintype "passive"))
      (node (ref "U7") (pin "2") (pinfunction "VREG5_2") (pintype "power_in"))
    )
    (net (code "35") (name "Net-(U8-EN)") (class "Default")
      (node (ref "J12") (pin "A1") (pinfunction "A1_A1") (pintype "passive"))
      (node (ref "R37") (pin "1") (pinfunction "1_1") (pintype "passive"))
      (node (ref "U8") (pin "6") (pinfunction "EN_6") (pintype "input"))
    )
    (net (code "36") (name "Net-(U8-PG)") (class "Default")
      (node (ref "R40") (pin "1") (pinfunction "1_1") (pintype "passive"))
      (node (ref "TP24") (pin "1") (pinfunction "1_1") (pintype "passive"))
      (node (ref "U8") (pin "5") (pinfunction "PG_5") (pintype "open_collector"))
    )
    (net (code "37") (name "Net-(U8-SS)") (class "Default")
      (node (ref "C40") (pin "2") (pinfunction "2_2") (pintype "passive"))
      (node (ref "U8") (pin "3") (pinfunction "SS_3") (pintype "input"))
    )
    (net (code "38") (name "Net-(U8-SW1)") (class "Default")
      (node (ref "C39") (pin "2") (pinfunction "2_2") (pintype "passive"))
      (node (ref "L7") (pin "1") (pinfunction "1_1") (pintype "passive"))
      (node (ref "U8") (pin "10") (pinfunction "SW2_10") (pintype "power_in"))
      (node (ref "U8") (pin "9") (pinfunction "SW1_9") (pintype "power_in"))
    )
    (net (code "39") (name "Net-(U8-VBST)") (class "Default")
      (node (ref "C39") (pin "1") (pinfunction "1_1") (pintype "passive"))
      (node (ref "U8") (pin "12") (pinfunction "VBST_12") (pintype "passive"))
    )
    (net (code "40") (name "Net-(U8-VFB)") (class "Default")
      (node (ref "R38") (pin "2") (pinfunction "2_2") (pintype "passive"))
      (node (ref "R39") (pin "1") (pinfunction "1_1") (pintype "passive"))
      (node (ref "U8") (pin "1") (pinfunction "VFB_1") (pintype "input"))
    )
    (net (code "41") (name "Net-(U8-VO)") (class "Default")
      (node (ref "C41") (pin "1") (pinfunction "1_1") (pintype "passive"))
      (node (ref "J11") (pin "1") (pinfunction "1_1") (pintype "passive"))
      (node (ref "L7") (pin "2") (pinfunction "2_2") (pintype "passive"))
      (node (ref "R39") (pin "2") (pinfunction "2_2") (pintype "passive"))
      (node (ref "TP23") (pin "1") (pinfunction "1_1") (pintype "passive"))
      (node (ref "U8") (pin "16") (pinfunction "VO_16") (pintype "input"))
    )
    (net (code "42") (name "Net-(U8-VREG5)") (class "Default")
      (node (ref "C38") (pin "2") (pinfunction "2_2") (pintype "passive"))
      (node (ref "R40") (pin "2") (pinfunction "2_2") (pintype "passive"))
      (node (ref "U8") (pin "2") (pinfunction "VREG5_2") (pintype "power_in"))
    )
  )
)
